# 5V_DC_DC.net
KiCad netlist of a schematic drawn in EAGLE
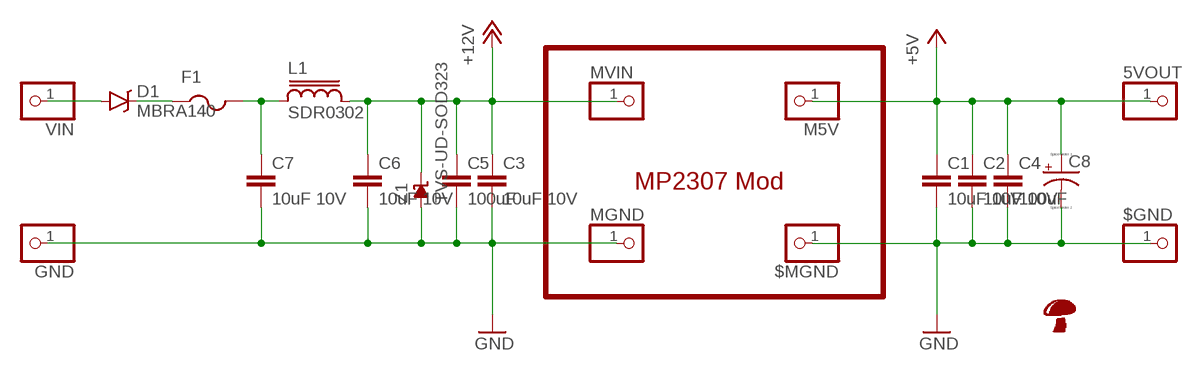
[diagram p0: schematic, sheet 1]

(export (version "E")
  (design (tool "Eeschema 10.0.6"))
  (components
    (comp (ref "$GND")
      (value "PINHD-1X1")
      (footprint "eagle-import:1X01")
      (libsource (lib "eagle-import") (part "PINHD-1X1"))
    )
    (comp (ref "$MGND")
      (value "PINHD-1X1")
      (footprint "eagle-import:1X01")
      (libsource (lib "eagle-import") (part "PINHD-1X1"))
    )
    (comp (ref "5VOUT")
      (value "PINHD-1X1")
      (footprint "eagle-import:1X01")
      (libsource (lib "eagle-import") (part "PINHD-1X1"))
    )
    (comp (ref "C1")
      (value "10uF 10V")
      (footprint "eagle-import:C0805")
      (libsource (lib "eagle-import") (part "C-EUC0805"))
    )
    (comp (ref "C2")
      (value "10uF 10V")
      (footprint "eagle-import:C0805")
      (libsource (lib "eagle-import") (part "C-EUC0805"))
    )
    (comp (ref "C3")
      (value "10uF 10V")
      (footprint "eagle-import:C0805")
      (libsource (lib "eagle-import") (part "C-EUC0805"))
    )
    (comp (ref "C4")
      (value "100uF")
      (footprint "eagle-import:C1206")
      (libsource (lib "eagle-import") (part "C-EUC1206"))
    )
    (comp (ref "C5")
      (value "100uF")
      (footprint "eagle-import:C1206")
      (libsource (lib "eagle-import") (part "C-EUC1206"))
    )
    (comp (ref "C6")
      (value "10uF 10V")
      (footprint "eagle-import:C0805")
      (libsource (lib "eagle-import") (part "C-EUC0805"))
    )
    (comp (ref "C7")
      (value "10uF 10V")
      (footprint "eagle-import:C0805")
      (libsource (lib "eagle-import") (part "C-EUC0805"))
    )
    (comp (ref "C8")
      (value "CPOL-USD")
      (footprint "eagle-import:PANASONIC_D")
      (libsource (lib "eagle-import") (part "CPOL-USD"))
    )
    (comp (ref "D1")
      (value "MBRA140")
      (footprint "eagle-import:SMA-DIODE")
      (libsource (lib "eagle-import") (part "MBRA140"))
    )
    (comp (ref "F1")
      (value "PTCFUSE-1812")
      (footprint "eagle-import:1812")
      (libsource (lib "eagle-import") (part "PTCFUSE-1812"))
    )
    (comp (ref "GND")
      (value "PINHD-1X1")
      (footprint "eagle-import:1X01")
      (libsource (lib "eagle-import") (part "PINHD-1X1"))
    )
    (comp (ref "L1")
      (value "SDR0302")
      (footprint "eagle-import:SDR0302")
      (libsource (lib "eagle-import") (part "SDR0302"))
    )
    (comp (ref "M5V")
      (value "PINHD-1X1")
      (footprint "eagle-import:1X01")
      (libsource (lib "eagle-import") (part "PINHD-1X1"))
    )
    (comp (ref "MGND")
      (value "PINHD-1X1")
      (footprint "eagle-import:1X01")
      (libsource (lib "eagle-import") (part "PINHD-1X1"))
    )
    (comp (ref "MVIN")
      (value "PINHD-1X1")
      (footprint "eagle-import:1X01")
      (libsource (lib "eagle-import") (part "PINHD-1X1"))
    )
    (comp (ref "U$1")
      (value "SHROOM5MM")
      (footprint "eagle-import:SHROOM")
      (libsource (lib "eagle-import") (part "SHROOM5MM"))
    )
    (comp (ref "VIN")
      (value "PINHD-1X1")
      (footprint "eagle-import:1X01")
      (libsource (lib "eagle-import") (part "PINHD-1X1"))
    )
    (comp (ref "Z1")
      (value "TVS-UD-SOD323")
      (footprint "eagle-import:SOD323")
      (libsource (lib "eagle-import") (part "TVS-UD-SOD323"))
    )
  )
  (nets
    (net (code "1") (name "+5V") (class "Default")
      (node (ref "5VOUT") (pin "1") (pinfunction "1_1") (pintype "passive"))
      (node (ref "C1") (pin "1") (pinfunction "1_1") (pintype "passive"))
      (node (ref "C2") (pin "1") (pinfunction "1_1") (pintype "passive"))
      (node (ref "C4") (pin "1") (pinfunction "1_1") (pintype "passive"))
      (node (ref "C8") (pin "+") (pinfunction "+_+") (pintype "passive"))
      (node (ref "M5V") (pin "1") (pinfunction "1_1") (pintype "passive"))
    )
    (net (code "2") (name "+12V") (class "Default")
      (node (ref "C3") (pin "1") (pinfunction "1_1") (pintype "passive"))
      (node (ref "C5") (pin "1") (pinfunction "1_1") (pintype "passive"))
      (node (ref "C6") (pin "1") (pinfunction "1_1") (pintype "passive"))
      (node (ref "L1") (pin "2") (pinfunction "2_2") (pintype "passive"))
      (node (ref "MVIN") (pin "1") (pinfunction "1_1") (pintype "passive"))
      (node (ref "Z1") (pin "C") (pinfunction "C_C") (pintype "passive"))
    )
    (net (code "3") (name "GND") (class "Default")
      (node (ref "$GND") (pin "1") (pinfunction "1_1") (pintype "passive"))
      (node (ref "$MGND") (pin "1") (pinfunction "1_1") (pintype "passive"))
      (node (ref "C1") (pin "2") (pinfunction "2_2") (pintype "passive"))
      (node (ref "C2") (pin "2") (pinfunction "2_2") (pintype "passive"))
      (node (ref "C3") (pin "2") (pinfunction "2_2") (pintype "passive"))
      (node (ref "C4") (pin "2") (pinfunction "2_2") (pintype "passive"))
      (node (ref "C5") (pin "2") (pinfunction "2_2") (pintype "passive"))
      (node (ref "C6") (pin "2") (pinfunction "2_2") (pintype "passive"))
      (node (ref "C7") (pin "2") (pinfunction "2_2") (pintype "passive"))
      (node (ref "C8") (pin "-") (pinfunction "-_-") (pintype "passive"))
      (node (ref "GND") (pin "1") (pinfunction "1_1") (pintype "passive"))
      (node (ref "MGND") (pin "1") (pinfunction "1_1") (pintype "passive"))
      (node (ref "Z1") (pin "A") (pinfunction "A_A") (pintype "passive"))
    )
    (net (code "4") (name "Net-(C7-Pad1)") (class "Default")
      (node (ref "C7") (pin "1") (pinfunction "1_1") (pintype "passive"))
      (node (ref "F1") (pin "2") (pinfunction "2_2") (pintype "passive"))
      (node (ref "L1") (pin "1") (pinfunction "1_1") (pintype "passive"))
    )
    (net (code "5") (name "Net-(D1-PadA)") (class "Default")
      (node (ref "D1") (pin "A") (pinfunction "A_A") (pintype "passive"))
      (node (ref "VIN") (pin "1") (pinfunction "1_1") (pintype "passive"))
    )
    (net (code "6") (name "Net-(D1-PadC)") (class "Default")
      (node (ref "D1") (pin "C") (pinfunction "C_C") (pintype "passive"))
      (node (ref "F1") (pin "1") (pinfunction "1_1") (pintype "passive"))
    )
  )
)
